# Temperature_Monitoring.net
KiCad netlist of a schematic drawn in Altium Designer
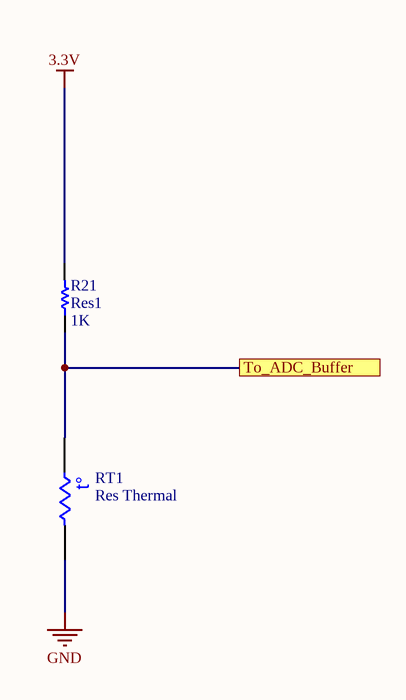
[diagram p0: Temperature_Monitoring.SchDoc]

(export (version "E")
  (design (tool "Eeschema 10.0.6"))
  (components
    (comp (ref "R21")
      (value "Res1")
      (footprint "AXIAL-0.3")
      (description "Resistor")
      (fields (field (name "ALTIUM_VALUE") "1K") (field (name "PUBLISHER") "Altium Limited"))
      (libsource (lib "Miscellaneous Devices") (part "Res1"))
    )
    (comp (ref "RT1")
      (value "Res Thermal")
      (footprint "6-0805_N")
      (description "Thermistor")
      (fields (field (name "PUBLISHER") "Altium Limited"))
      (libsource (lib "Miscellaneous Devices") (part "Res Thermal"))
    )
  )
  (nets
    (net (code "1") (name "/To_ADC_Buffer") (class "Default")
      (node (ref "R21") (pin "1") (pinfunction "1_1") (pintype "passive"))
      (node (ref "RT1") (pin "1") (pinfunction "1_1") (pintype "passive"))
    )
    (net (code "2") (name "3.3V") (class "Default")
      (node (ref "R21") (pin "2") (pinfunction "2_2") (pintype "passive"))
    )
    (net (code "3") (name "GND") (class "Default")
      (node (ref "RT1") (pin "2") (pinfunction "2_2") (pintype "passive"))
    )
  )
)
